# dsau-power.net
KiCad netlist of a schematic drawn in Altium Designer
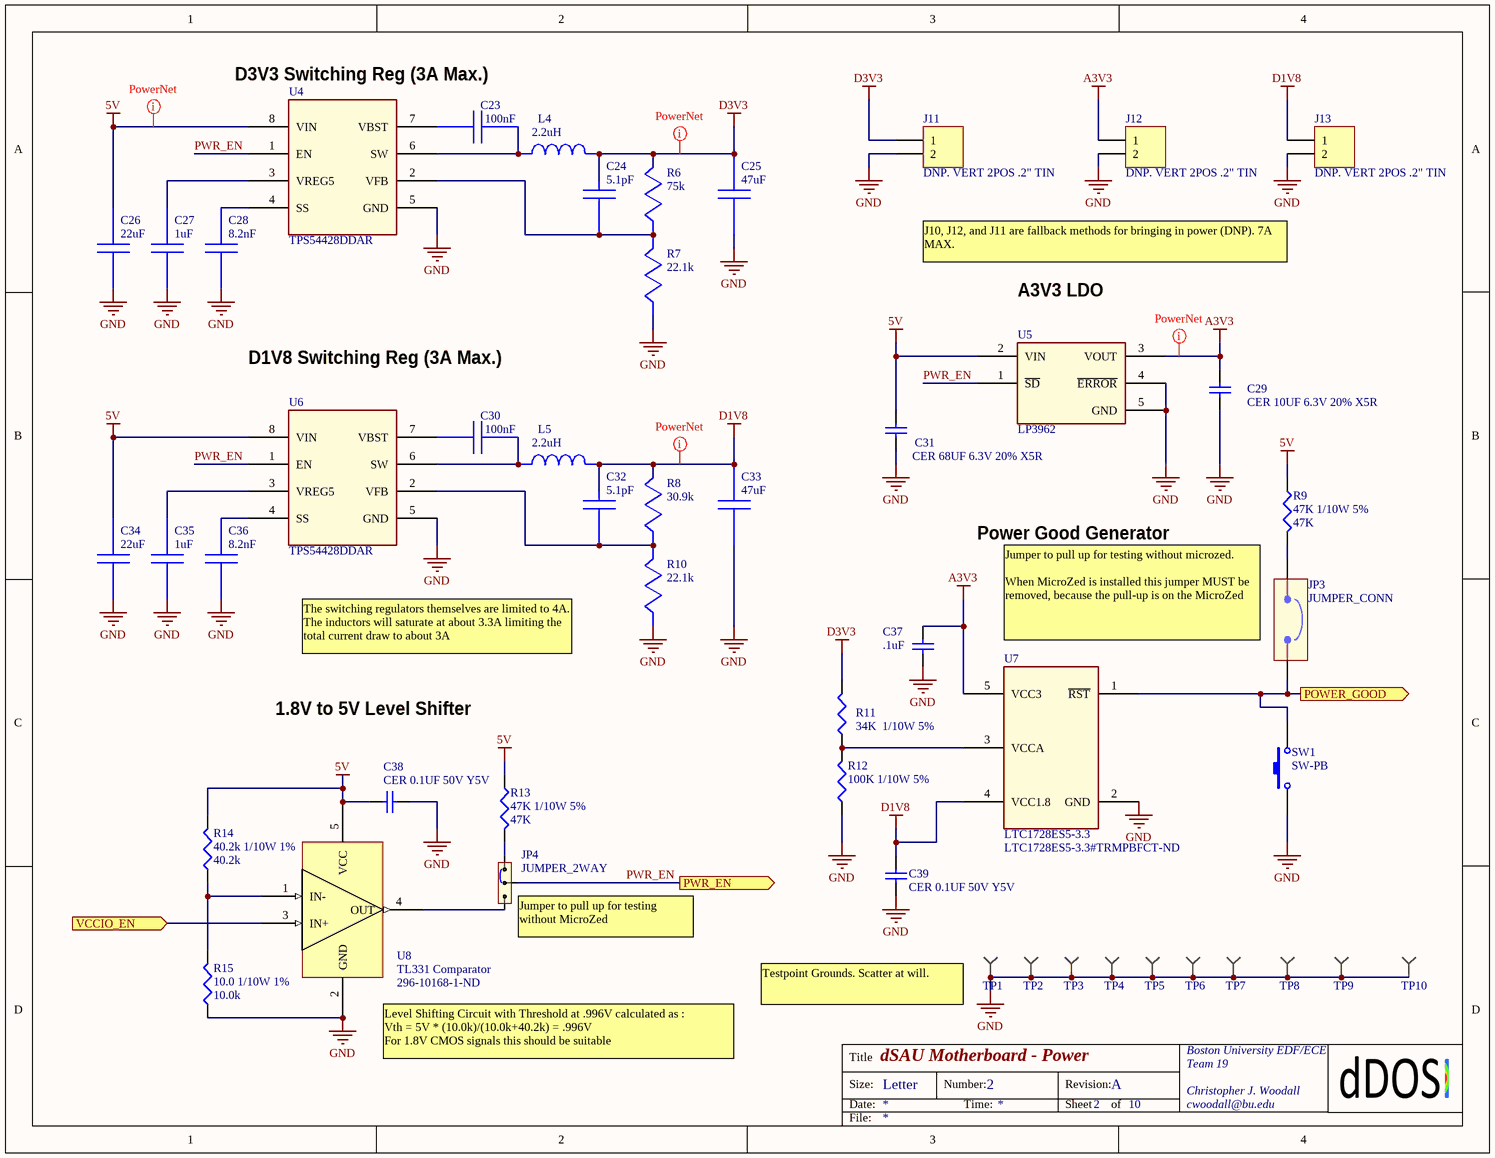
[diagram p0: dsau-power.SchDoc]

(export (version "E")
  (design (tool "Eeschema 10.0.6"))
  (components
    (comp (ref "C23")
      (value "100nF")
      (footprint "0402")
      (fields (field (name "MANUFACTURER PART NUMBER") "C1005X5R1A104K"))
      (libsource (lib "TI WEBENCH") (part "Cboot_1"))
    )
    (comp (ref "C24")
      (value "5.1pF")
      (footprint "0402")
      (description "GRM1555C1E5R1CA0")
      (fields (field (name "MANUFACTURER PART NUMBER") "C0402C519C5GACTU"))
      (libsource (lib "TI WEBENCH") (part "Cff_1"))
    )
    (comp (ref "C25")
      (value "47uF")
      (footprint "1206")
      (description "GRM31CR60J476ME1")
      (fields (field (name "MANUFACTURER PART NUMBER") "GRM31CR60J476ME19L"))
      (libsource (lib "TI WEBENCH") (part "Cout_1"))
    )
    (comp (ref "C26")
      (value "22uF")
      (footprint "1210")
      (description "C3225X5R1A226M")
      (libsource (lib "TI WEBENCH") (part "Cin_1"))
    )
    (comp (ref "C27")
      (value "1uF")
      (footprint "0402")
      (description "GRM155R61A105KE1")
      (fields (field (name "MANUFACTURER PART NUMBER") "GRM155R61A105KE15D"))
      (libsource (lib "TI WEBENCH") (part "Creg_1"))
    )
    (comp (ref "C28")
      (value "8.2nF")
      (footprint "0402")
      (description "GRM155R71E822KA0")
      (fields (field (name "MANUFACTURER PART NUMBER") "GRM155R71E822KA01D"))
      (libsource (lib "TI WEBENCH") (part "Css_1"))
    )
    (comp (ref "C29")
      (value "CER 10UF 6.3V 20% X5R")
      (footprint "CAPC1608L")
      (description "Capacitor")
      (fields
        (field (name "MANUFACTURER") "Samsung Electro-Mechanics America, Inc")
        (field (name "MANUFACTURER PART NUMBER") "CL10A106MQ8NNNC")
        (field (name "PUBLISHER") "Altium Limited")
      )
      (libsource (lib "Miscellaneous Devices") (part "Cap"))
    )
    (comp (ref "C30")
      (value "100nF")
      (footprint "0402")
      (fields (field (name "MANUFACTURER PART NUMBER") "C1005X5R1A104K"))
      (libsource (lib "TI WEBENCH") (part "Cboot_1"))
    )
    (comp (ref "C31")
      (value "CER 68UF 6.3V 20% X5R")
      (footprint "CAPC3216L")
      (description "Capacitor")
      (fields
        (field (name "MANUFACTURER") "TDK Corporation")
        (field (name "MANUFACTURER PART NUMBER") "C3216X5R0J686M160AB")
        (field (name "PUBLISHER") "Altium Limited")
      )
      (libsource (lib "Miscellaneous Devices") (part "Cap"))
    )
    (comp (ref "C32")
      (value "5.1pF")
      (footprint "0402")
      (description "GRM1555C1E5R1CA0")
      (fields (field (name "MANUFACTURER PART NUMBER") "C0402C519C5GACTU"))
      (libsource (lib "TI WEBENCH") (part "Cff_1"))
    )
    (comp (ref "C33")
      (value "47uF")
      (footprint "1206")
      (description "GRM31CR60J476ME1")
      (fields (field (name "MANUFACTURER PART NUMBER") "GRM31CR60J476ME19L"))
      (libsource (lib "TI WEBENCH") (part "Cout_1"))
    )
    (comp (ref "C34")
      (value "22uF")
      (footprint "1210")
      (description "C3225X5R1A226M")
      (libsource (lib "TI WEBENCH") (part "Cin_1"))
    )
    (comp (ref "C35")
      (value "1uF")
      (footprint "0402")
      (description "GRM155R61A105KE1")
      (fields (field (name "MANUFACTURER PART NUMBER") "GRM155R61A105KE15D"))
      (libsource (lib "TI WEBENCH") (part "Creg_1"))
    )
    (comp (ref "C36")
      (value "8.2nF")
      (footprint "0402")
      (description "GRM155R71E822KA0")
      (fields (field (name "MANUFACTURER PART NUMBER") "GRM155R71E822KA01D"))
      (libsource (lib "TI WEBENCH") (part "Css_1"))
    )
    (comp (ref "C37")
      (value ".1uF")
      (footprint "CAPC1608L")
      (description "Capacitor")
      (fields
        (field (name "MANUFACTURER") "Yageo")
        (field (name "MANUFACTURER PART NUMBER") "CC0603ZRY5V9BB104")
        (field (name "PUBLISHER") "Altium Limited")
      )
      (libsource (lib "Miscellaneous Devices") (part "Cap"))
    )
    (comp (ref "C38")
      (value "CER 0.1UF 50V Y5V")
      (footprint "CAPC1608L")
      (description "Capacitor")
      (fields
        (field (name "MANUFACTURER") "Yageo")
        (field (name "MANUFACTURER PART NUMBER") "CC0603ZRY5V9BB104")
        (field (name "PUBLISHER") "Altium Limited")
      )
      (libsource (lib "Miscellaneous Devices") (part "Cap"))
    )
    (comp (ref "C39")
      (value "CER 0.1UF 50V Y5V")
      (footprint "CAPC1608L")
      (description "Capacitor")
      (fields
        (field (name "MANUFACTURER") "Yageo")
        (field (name "MANUFACTURER PART NUMBER") "CC0603ZRY5V9BB104")
        (field (name "PUBLISHER") "Altium Limited")
      )
      (libsource (lib "Miscellaneous Devices") (part "Cap"))
    )
    (comp (ref "J11")
      (value "DNP. VERT 2POS .2\" TIN")
      (footprint "MOLEX_2POS_200mil_0010085021")
      (description "Header, 2-Pin")
      (fields
        (field (name "MANUFACTURER") "Molex Inc")
        (field (name "MANUFACTURER PART NUMBER") "0010085021")
        (field (name "PUBLISHER") "Altium Limited")
      )
      (libsource (lib "Miscellaneous Connectors") (part "Header 2"))
    )
    (comp (ref "J12")
      (value "DNP. VERT 2POS .2\" TIN")
      (footprint "MOLEX_2POS_200mil_0010085021")
      (description "Header, 2-Pin")
      (fields
        (field (name "MANUFACTURER") "Molex Inc")
        (field (name "MANUFACTURER PART NUMBER") "0010085021")
        (field (name "PUBLISHER") "Altium Limited")
      )
      (libsource (lib "Miscellaneous Connectors") (part "Header 2"))
    )
    (comp (ref "J13")
      (value "DNP. VERT 2POS .2\" TIN")
      (footprint "MOLEX_2POS_200mil_0010085021")
      (description "Header, 2-Pin")
      (fields
        (field (name "MANUFACTURER") "Molex Inc")
        (field (name "MANUFACTURER PART NUMBER") "0010085021")
        (field (name "PUBLISHER") "Altium Limited")
      )
      (libsource (lib "Miscellaneous Connectors") (part "Header 2"))
    )
    (comp (ref "JP3")
      (value "JUMPER_CONN")
      (footprint "HDR1X2")
      (libsource (lib "dsau-motherboard") (part "JUMPER_CONN"))
    )
    (comp (ref "JP4")
      (value "JUMPER_2WAY")
      (footprint "HDR1X3")
      (libsource (lib "dsau-motherboard") (part "JUMPER_2WAY"))
    )
    (comp (ref "L4")
      (value "2.2uH")
      (footprint "SRN6045")
      (description "SRN6045-2R2Y")
      (libsource (lib "TI WEBENCH") (part "L1"))
    )
    (comp (ref "L5")
      (value "2.2uH")
      (footprint "SRN6045")
      (description "SRN6045-2R2Y")
      (libsource (lib "TI WEBENCH") (part "L1"))
    )
    (comp (ref "R6")
      (value "75k")
      (footprint "0402")
      (description "CRCW040275K0FKED")
      (libsource (lib "TI WEBENCH") (part "Rfbt_1"))
    )
    (comp (ref "R7")
      (value "22.1k")
      (footprint "0402")
      (description "CRCW040222K1FKED")
      (libsource (lib "TI WEBENCH") (part "Rfbb_1"))
    )
    (comp (ref "R8")
      (value "30.9k")
      (footprint "0402")
      (description "CRCW040230K9FKED")
      (libsource (lib "TI WEBENCH") (part "Rfbt_1"))
    )
    (comp (ref "R9")
      (value "47K 1/10W 5%")
      (footprint "RESC1608L")
      (description "Resistor")
      (fields
        (field (name "ALTIUM_VALUE") "47K")
        (field (name "MANUFACTURER") "Yageo")
        (field (name "MANUFACTURER PART NUMBER") "311-47kGRCT-ND")
        (field (name "PUBLISHER") "Altium Limited")
      )
      (libsource (lib "Miscellaneous Devices") (part "Res3"))
    )
    (comp (ref "R10")
      (value "22.1k")
      (footprint "0402")
      (description "CRCW040222K1FKED")
      (libsource (lib "TI WEBENCH") (part "Rfbb_1"))
    )
    (comp (ref "R11")
      (value "34K  1/10W 5%")
      (footprint "RESC1608L")
      (description "Resistor")
      (fields
        (field (name "MANUFACTURER") "Yageo")
        (field (name "MANUFACTURER PART NUMBER") "RT0603DRD0734KL")
        (field (name "PUBLISHER") "Altium Limited")
      )
      (libsource (lib "Miscellaneous Devices") (part "Res3"))
    )
    (comp (ref "R12")
      (value "100K 1/10W 5%")
      (footprint "RESC1608L")
      (description "Resistor")
      (fields
        (field (name "MANUFACTURER") "Yageo")
        (field (name "MANUFACTURER PART NUMBER") "RC0603JR-07100KL")
        (field (name "PUBLISHER") "Altium Limited")
      )
      (libsource (lib "Miscellaneous Devices") (part "Res3"))
    )
    (comp (ref "R13")
      (value "47K 1/10W 5%")
      (footprint "RESC1608L")
      (description "Resistor")
      (fields
        (field (name "ALTIUM_VALUE") "47K")
        (field (name "MANUFACTURER") "Yageo")
        (field (name "MANUFACTURER PART NUMBER") "311-47kGRCT-ND")
        (field (name "PUBLISHER") "Altium Limited")
      )
      (libsource (lib "Miscellaneous Devices") (part "Res3"))
    )
    (comp (ref "R14")
      (value "40.2k 1/10W 1%")
      (footprint "RESC1608L")
      (description "Resistor")
      (fields
        (field (name "ALTIUM_VALUE") "40.2k")
        (field (name "MANUFACTURER") "Yageo")
        (field (name "MANUFACTURER PART NUMBER") "RC0603FR-0740K2L")
        (field (name "PUBLISHER") "Altium Limited")
      )
      (libsource (lib "Miscellaneous Devices") (part "Res3"))
    )
    (comp (ref "R15")
      (value "10.0 1/10W 1%")
      (footprint "RESC1608L")
      (description "Resistor")
      (fields
        (field (name "ALTIUM_VALUE") "10.0k")
        (field (name "MANUFACTURER") "Yageo")
        (field (name "MANUFACTURER PART NUMBER") "RC0603FR-07220RL")
        (field (name "PUBLISHER") "Altium Limited")
      )
      (libsource (lib "Miscellaneous Devices") (part "Res3"))
    )
    (comp (ref "SW1")
      (value "SW-PB")
      (footprint "SPST_SW_FSM4JH")
      (description "Switch")
      (fields
        (field (name "MANUFACTURER") "TE Connectivity")
        (field (name "MANUFACTURER PART NUMBER") "FSM4JH")
        (field (name "PUBLISHER") "Altium Limited")
      )
      (libsource (lib "Miscellaneous Devices") (part "SW-PB"))
    )
    (comp (ref "TP1")
      (value "TESTPOINT_CW")
      (footprint "PIN1")
      (fields (field (name "MANUFACTURER") "Keystone") (field (name "MANUFACTURER PART NUMBER") "5000"))
      (libsource (lib "dsau-motherboard") (part "TESTPOINT_CW"))
    )
    (comp (ref "TP2")
      (value "TESTPOINT_CW")
      (footprint "PIN1")
      (fields (field (name "MANUFACTURER") "Keystone") (field (name "MANUFACTURER PART NUMBER") "5000"))
      (libsource (lib "dsau-motherboard") (part "TESTPOINT_CW"))
    )
    (comp (ref "TP3")
      (value "TESTPOINT_CW")
      (footprint "PIN1")
      (fields (field (name "MANUFACTURER") "Keystone") (field (name "MANUFACTURER PART NUMBER") "5000"))
      (libsource (lib "dsau-motherboard") (part "TESTPOINT_CW"))
    )
    (comp (ref "TP4")
      (value "TESTPOINT_CW")
      (footprint "PIN1")
      (fields (field (name "MANUFACTURER") "Keystone") (field (name "MANUFACTURER PART NUMBER") "5000"))
      (libsource (lib "dsau-motherboard") (part "TESTPOINT_CW"))
    )
    (comp (ref "TP5")
      (value "TESTPOINT_CW")
      (footprint "PIN1")
      (fields (field (name "MANUFACTURER") "Keystone") (field (name "MANUFACTURER PART NUMBER") "5000"))
      (libsource (lib "dsau-motherboard") (part "TESTPOINT_CW"))
    )
    (comp (ref "TP6")
      (value "TESTPOINT_CW")
      (footprint "PIN1")
      (fields (field (name "MANUFACTURER") "Keystone") (field (name "MANUFACTURER PART NUMBER") "5000"))
      (libsource (lib "dsau-motherboard") (part "TESTPOINT_CW"))
    )
    (comp (ref "TP7")
      (value "TESTPOINT_CW")
      (footprint "PIN1")
      (fields (field (name "MANUFACTURER") "Keystone") (field (name "MANUFACTURER PART NUMBER") "5000"))
      (libsource (lib "dsau-motherboard") (part "TESTPOINT_CW"))
    )
    (comp (ref "TP8")
      (value "TESTPOINT_CW")
      (footprint "PIN1")
      (fields (field (name "MANUFACTURER") "Keystone") (field (name "MANUFACTURER PART NUMBER") "5000"))
      (libsource (lib "dsau-motherboard") (part "TESTPOINT_CW"))
    )
    (comp (ref "TP9")
      (value "TESTPOINT_CW")
      (footprint "PIN1")
      (fields (field (name "MANUFACTURER") "Keystone") (field (name "MANUFACTURER PART NUMBER") "5000"))
      (libsource (lib "dsau-motherboard") (part "TESTPOINT_CW"))
    )
    (comp (ref "TP10")
      (value "TESTPOINT_CW")
      (footprint "PIN1")
      (fields (field (name "MANUFACTURER") "Keystone") (field (name "MANUFACTURER PART NUMBER") "5000"))
      (libsource (lib "dsau-motherboard") (part "TESTPOINT_CW"))
    )
    (comp (ref "U4")
      (value "TPS54428DDAR")
      (footprint "R-PDSO-G8")
      (description "Imported")
      (fields (field (name "MANUFACTURER") "Texas Instruments"))
      (libsource (lib "3vreg") (part "TPS54428DDAR"))
    )
    (comp (ref "U5")
      (value "LP3962")
      (footprint "SOT223-5N")
      (fields
        (field (name "MANUFACTURER") "Texas Instruments")
        (field (name "MANUFACTURER PART NUMBER") "LP3962EMP-3.3/NOPB")
      )
      (libsource (lib "dsau_power") (part "LP3962"))
    )
    (comp (ref "U6")
      (value "TPS54428DDAR")
      (footprint "R-PDSO-G8")
      (description "Imported")
      (fields (field (name "MANUFACTURER") "Texas Instruments"))
      (libsource (lib "3vreg") (part "TPS54428DDAR"))
    )
    (comp (ref "U7")
      (value "LTC1728ES5-3.3")
      (footprint "SOT23_5L_CUSTOM")
      (fields
        (field (name "SUPPLIER PART NUMBER 1") "LTC1728ES5-3.3#TRMPBFCT-ND")
        (field (name "MANUFACTURER") "Linear Technology")
        (field (name "MANUFACTURER PART NUMBER") "LTC1728ES5-3.3#TRMPBF")
      )
      (libsource (lib "dsau_power") (part "LTC1728ES5-3.3"))
    )
    (comp (ref "U8")
      (value "TL331 Comparator")
      (footprint "SOT23_5L_CUSTOM")
      (fields
        (field (name "MANUFACTURER PART NUMBER") "TL331IDBVR")
        (field (name "MANUFACTURER") "Texas Instruments")
        (field (name "SUPPLIER PART NUMBER 1") "296-10168-1-ND")
      )
      (libsource (lib "dsau-motherboard") (part "TL331"))
    )
  )
  (nets
    (net (code "1") (name "/POWER_GOOD") (class "Default")
      (node (ref "JP3") (pin "1") (pintype "passive"))
      (node (ref "SW1") (pin "1") (pinfunction "1_1") (pintype "passive"))
      (node (ref "U7") (pin "1") (pinfunction "~{RST}_1") (pintype "passive"))
    )
    (net (code "2") (name "/PWR_EN") (class "Default")
      (node (ref "JP4") (pin "2") (pintype "passive"))
      (node (ref "U4") (pin "1") (pinfunction "EN_1") (pintype "passive"))
      (node (ref "U5") (pin "1") (pinfunction "~{SD}_1") (pintype "passive"))
      (node (ref "U6") (pin "1") (pinfunction "EN_1") (pintype "passive"))
    )
    (net (code "3") (name "/VCCIO_EN") (class "Default")
      (node (ref "U8") (pin "3") (pinfunction "IN+_3") (pintype "input"))
    )
    (net (code "4") (name "5V") (class "Default")
      (node (ref "C26") (pin "1") (pinfunction "1_1") (pintype "passive"))
      (node (ref "C31") (pin "2") (pinfunction "2_2") (pintype "passive"))
      (node (ref "C34") (pin "1") (pinfunction "1_1") (pintype "passive"))
      (node (ref "C38") (pin "1") (pinfunction "1_1") (pintype "passive"))
      (node (ref "R13") (pin "1") (pinfunction "1_1") (pintype "passive"))
      (node (ref "R14") (pin "2") (pinfunction "2_2") (pintype "passive"))
      (node (ref "R9") (pin "1") (pinfunction "1_1") (pintype "passive"))
      (node (ref "U4") (pin "8") (pinfunction "VIN_8") (pintype "passive"))
      (node (ref "U5") (pin "2") (pinfunction "VIN_2") (pintype "passive"))
      (node (ref "U6") (pin "8") (pinfunction "VIN_8") (pintype "passive"))
      (node (ref "U8") (pin "5") (pinfunction "VCC_5") (pintype "power_in"))
    )
    (net (code "5") (name "A3V3") (class "Default")
      (node (ref "C29") (pin "2") (pinfunction "2_2") (pintype "passive"))
      (node (ref "C37") (pin "1") (pinfunction "1_1") (pintype "passive"))
      (node (ref "J12") (pin "1") (pinfunction "1_1") (pintype "passive"))
      (node (ref "U5") (pin "3") (pinfunction "VOUT_3") (pintype "passive"))
      (node (ref "U7") (pin "5") (pinfunction "VCC3_5") (pintype "passive"))
    )
    (net (code "6") (name "D1V8") (class "Default")
      (node (ref "C32") (pin "1") (pinfunction "1_1") (pintype "passive"))
      (node (ref "C33") (pin "1") (pinfunction "1_1") (pintype "passive"))
      (node (ref "C39") (pin "2") (pinfunction "2_2") (pintype "passive"))
      (node (ref "J13") (pin "1") (pinfunction "1_1") (pintype "passive"))
      (node (ref "L5") (pin "1") (pinfunction "1_1") (pintype "passive"))
      (node (ref "R8") (pin "1") (pinfunction "1_1") (pintype "passive"))
      (node (ref "U7") (pin "4") (pinfunction "VCC1.8_4") (pintype "passive"))
    )
    (net (code "7") (name "D3V3") (class "Default")
      (node (ref "C24") (pin "1") (pinfunction "1_1") (pintype "passive"))
      (node (ref "C25") (pin "1") (pinfunction "1_1") (pintype "passive"))
      (node (ref "J11") (pin "1") (pinfunction "1_1") (pintype "passive"))
      (node (ref "L4") (pin "1") (pinfunction "1_1") (pintype "passive"))
      (node (ref "R11") (pin "2") (pinfunction "2_2") (pintype "passive"))
      (node (ref "R6") (pin "1") (pinfunction "1_1") (pintype "passive"))
    )
    (net (code "8") (name "GND") (class "Default")
      (node (ref "C25") (pin "2") (pinfunction "2_2") (pintype "passive"))
      (node (ref "C26") (pin "2") (pinfunction "2_2") (pintype "passive"))
      (node (ref "C27") (pin "2") (pinfunction "2_2") (pintype "passive"))
      (node (ref "C28") (pin "2") (pinfunction "2_2") (pintype "passive"))
      (node (ref "C29") (pin "1") (pinfunction "1_1") (pintype "passive"))
      (node (ref "C31") (pin "1") (pinfunction "1_1") (pintype "passive"))
      (node (ref "C33") (pin "2") (pinfunction "2_2") (pintype "passive"))
      (node (ref "C34") (pin "2") (pinfunction "2_2") (pintype "passive"))
      (node (ref "C35") (pin "2") (pinfunction "2_2") (pintype "passive"))
      (node (ref "C36") (pin "2") (pinfunction "2_2") (pintype "passive"))
      (node (ref "C37") (pin "2") (pinfunction "2_2") (pintype "passive"))
      (node (ref "C38") (pin "2") (pinfunction "2_2") (pintype "passive"))
      (node (ref "C39") (pin "1") (pinfunction "1_1") (pintype "passive"))
      (node (ref "J11") (pin "2") (pinfunction "2_2") (pintype "passive"))
      (node (ref "J12") (pin "2") (pinfunction "2_2") (pintype "passive"))
      (node (ref "J13") (pin "2") (pinfunction "2_2") (pintype "passive"))
      (node (ref "R10") (pin "2") (pinfunction "2_2") (pintype "passive"))
      (node (ref "R12") (pin "1") (pinfunction "1_1") (pintype "passive"))
      (node (ref "R15") (pin "1") (pinfunction "1_1") (pintype "passive"))
      (node (ref "R7") (pin "2") (pinfunction "2_2") (pintype "passive"))
      (node (ref "SW1") (pin "2") (pinfunction "2_2") (pintype "passive"))
      (node (ref "TP1") (pin "1") (pintype "passive"))
      (node (ref "TP10") (pin "1") (pintype "passive"))
      (node (ref "TP2") (pin "1") (pintype "passive"))
      (node (ref "TP3") (pin "1") (pintype "passive"))
      (node (ref "TP4") (pin "1") (pintype "passive"))
      (node (ref "TP5") (pin "1") (pintype "passive"))
      (node (ref "TP6") (pin "1") (pintype "passive"))
      (node (ref "TP7") (pin "1") (pintype "passive"))
      (node (ref "TP8") (pin "1") (pintype "passive"))
      (node (ref "TP9") (pin "1") (pintype "passive"))
      (node (ref "U4") (pin "5") (pinfunction "GND_5") (pintype "passive"))
      (node (ref "U5") (pin "4") (pinfunction "~{ERROR}_4") (pintype "passive"))
      (node (ref "U5") (pin "5") (pinfunction "GND_5") (pintype "passive"))
      (node (ref "U6") (pin "5") (pinfunction "GND_5") (pintype "passive"))
      (node (ref "U7") (pin "2") (pinfunction "GND_2") (pintype "passive"))
      (node (ref "U8") (pin "2") (pinfunction "GND_2") (pintype "power_in"))
    )
    (net (code "9") (name "Net-(JP3-Pad2)") (class "Default")
      (node (ref "JP3") (pin "2") (pintype "passive"))
      (node (ref "R9") (pin "2") (pinfunction "2_2") (pintype "passive"))
    )
    (net (code "10") (name "Net-(JP4-Pad1)") (class "Default")
      (node (ref "JP4") (pin "1") (pintype "passive"))
      (node (ref "R13") (pin "2") (pinfunction "2_2") (pintype "passive"))
    )
    (net (code "11") (name "Net-(U4-SS)") (class "Default")
      (node (ref "C28") (pin "1") (pinfunction "1_1") (pintype "passive"))
      (node (ref "U4") (pin "4") (pinfunction "SS_4") (pintype "passive"))
    )
    (net (code "12") (name "Net-(U4-SW)") (class "Default")
      (node (ref "C23") (pin "2") (pinfunction "2_2") (pintype "passive"))
      (node (ref "L4") (pin "2") (pinfunction "2_2") (pintype "passive"))
      (node (ref "U4") (pin "6") (pinfunction "SW_6") (pintype "passive"))
    )
    (net (code "13") (name "Net-(U4-VBST)") (class "Default")
      (node (ref "C23") (pin "1") (pinfunction "1_1") (pintype "passive"))
      (node (ref "U4") (pin "7") (pinfunction "VBST_7") (pintype "passive"))
    )
    (net (code "14") (name "Net-(U4-VFB)") (class "Default")
      (node (ref "C24") (pin "2") (pinfunction "2_2") (pintype "passive"))
      (node (ref "R6") (pin "2") (pinfunction "2_2") (pintype "passive"))
      (node (ref "R7") (pin "1") (pinfunction "1_1") (pintype "passive"))
      (node (ref "U4") (pin "2") (pinfunction "VFB_2") (pintype "passive"))
    )
    (net (code "15") (name "Net-(U4-VREG5)") (class "Default")
      (node (ref "C27") (pin "1") (pinfunction "1_1") (pintype "passive"))
      (node (ref "U4") (pin "3") (pinfunction "VREG5_3") (pintype "passive"))
    )
    (net (code "16") (name "Net-(U6-SS)") (class "Default")
      (node (ref "C36") (pin "1") (pinfunction "1_1") (pintype "passive"))
      (node (ref "U6") (pin "4") (pinfunction "SS_4") (pintype "passive"))
    )
    (net (code "17") (name "Net-(U6-SW)") (class "Default")
      (node (ref "C30") (pin "2") (pinfunction "2_2") (pintype "passive"))
      (node (ref "L5") (pin "2") (pinfunction "2_2") (pintype "passive"))
      (node (ref "U6") (pin "6") (pinfunction "SW_6") (pintype "passive"))
    )
    (net (code "18") (name "Net-(U6-VBST)") (class "Default")
      (node (ref "C30") (pin "1") (pinfunction "1_1") (pintype "passive"))
      (node (ref "U6") (pin "7") (pinfunction "VBST_7") (pintype "passive"))
    )
    (net (code "19") (name "Net-(U6-VFB)") (class "Default")
      (node (ref "C32") (pin "2") (pinfunction "2_2") (pintype "passive"))
      (node (ref "R10") (pin "1") (pinfunction "1_1") (pintype "passive"))
      (node (ref "R8") (pin "2") (pinfunction "2_2") (pintype "passive"))
      (node (ref "U6") (pin "2") (pinfunction "VFB_2") (pintype "passive"))
    )
    (net (code "20") (name "Net-(U6-VREG5)") (class "Default")
      (node (ref "C35") (pin "1") (pinfunction "1_1") (pintype "passive"))
      (node (ref "U6") (pin "3") (pinfunction "VREG5_3") (pintype "passive"))
    )
    (net (code "21") (name "Net-(U7-VCCA)") (class "Default")
      (node (ref "R11") (pin "1") (pinfunction "1_1") (pintype "passive"))
      (node (ref "R12") (pin "2") (pinfunction "2_2") (pintype "passive"))
      (node (ref "U7") (pin "3") (pinfunction "VCCA_3") (pintype "passive"))
    )
    (net (code "22") (name "Net-(U8-IN-)") (class "Default")
      (node (ref "R14") (pin "1") (pinfunction "1_1") (pintype "passive"))
      (node (ref "R15") (pin "2") (pinfunction "2_2") (pintype "passive"))
      (node (ref "U8") (pin "1") (pinfunction "IN-_1") (pintype "input"))
    )
    (net (code "23") (name "Net-(U8-OUT)") (class "Default")
      (node (ref "JP4") (pin "3") (pintype "passive"))
      (node (ref "U8") (pin "4") (pinfunction "OUT_4") (pintype "output"))
    )
  )
)
